# CT310_IJ_V1_0.net
KiCad netlist of a schematic drawn in Altium Designer
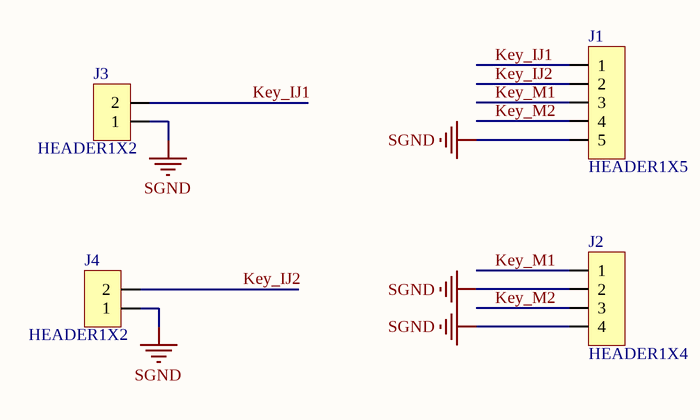
[diagram p0: CT310高端控制盒IJ区按键电路V1.0.SchDoc]

(export (version "E")
  (design (tool "Eeschema 10.0.6"))
  (components
    (comp (ref "J1")
      (value "HEADER1X5")
      (footprint "ZH1X5LT-1.5")
      (libsource (lib "Connector Class") (part "HEADER1X5"))
    )
    (comp (ref "J2")
      (value "HEADER1X4")
      (footprint "ZH1X4LT-1.5")
      (libsource (lib "Connector Class") (part "HEADER1X4"))
    )
    (comp (ref "J3")
      (value "HEADER1X2")
      (footprint "SW-MEC")
      (libsource (lib "Connector Class") (part "HEADER1X2"))
    )
    (comp (ref "J4")
      (value "HEADER1X2")
      (footprint "SW-MEC")
      (libsource (lib "Connector Class") (part "HEADER1X2"))
    )
  )
  (nets
    (net (code "1") (name "/Key_IJ1") (class "Default")
      (node (ref "J1") (pin "1") (pinfunction "1_1") (pintype "passive"))
      (node (ref "J3") (pin "2") (pinfunction "2_2") (pintype "passive"))
    )
    (net (code "2") (name "/Key_IJ2") (class "Default")
      (node (ref "J1") (pin "2") (pinfunction "2_2") (pintype "passive"))
      (node (ref "J4") (pin "2") (pinfunction "2_2") (pintype "passive"))
    )
    (net (code "3") (name "/Key_M1") (class "Default")
      (node (ref "J1") (pin "3") (pinfunction "3_3") (pintype "passive"))
      (node (ref "J2") (pin "1") (pinfunction "1_1") (pintype "passive"))
    )
    (net (code "4") (name "/Key_M2") (class "Default")
      (node (ref "J1") (pin "4") (pinfunction "4_4") (pintype "passive"))
      (node (ref "J2") (pin "3") (pinfunction "3_3") (pintype "passive"))
    )
    (net (code "5") (name "SGND") (class "Default")
      (node (ref "J1") (pin "5") (pinfunction "5_5") (pintype "passive"))
      (node (ref "J2") (pin "2") (pinfunction "2_2") (pintype "passive"))
      (node (ref "J2") (pin "4") (pinfunction "4_4") (pintype "passive"))
      (node (ref "J3") (pin "1") (pinfunction "1_1") (pintype "passive"))
      (node (ref "J4") (pin "1") (pinfunction "1_1") (pintype "passive"))
    )
  )
)
